# 0x02.net
KiCad netlist of a schematic drawn in EAGLE
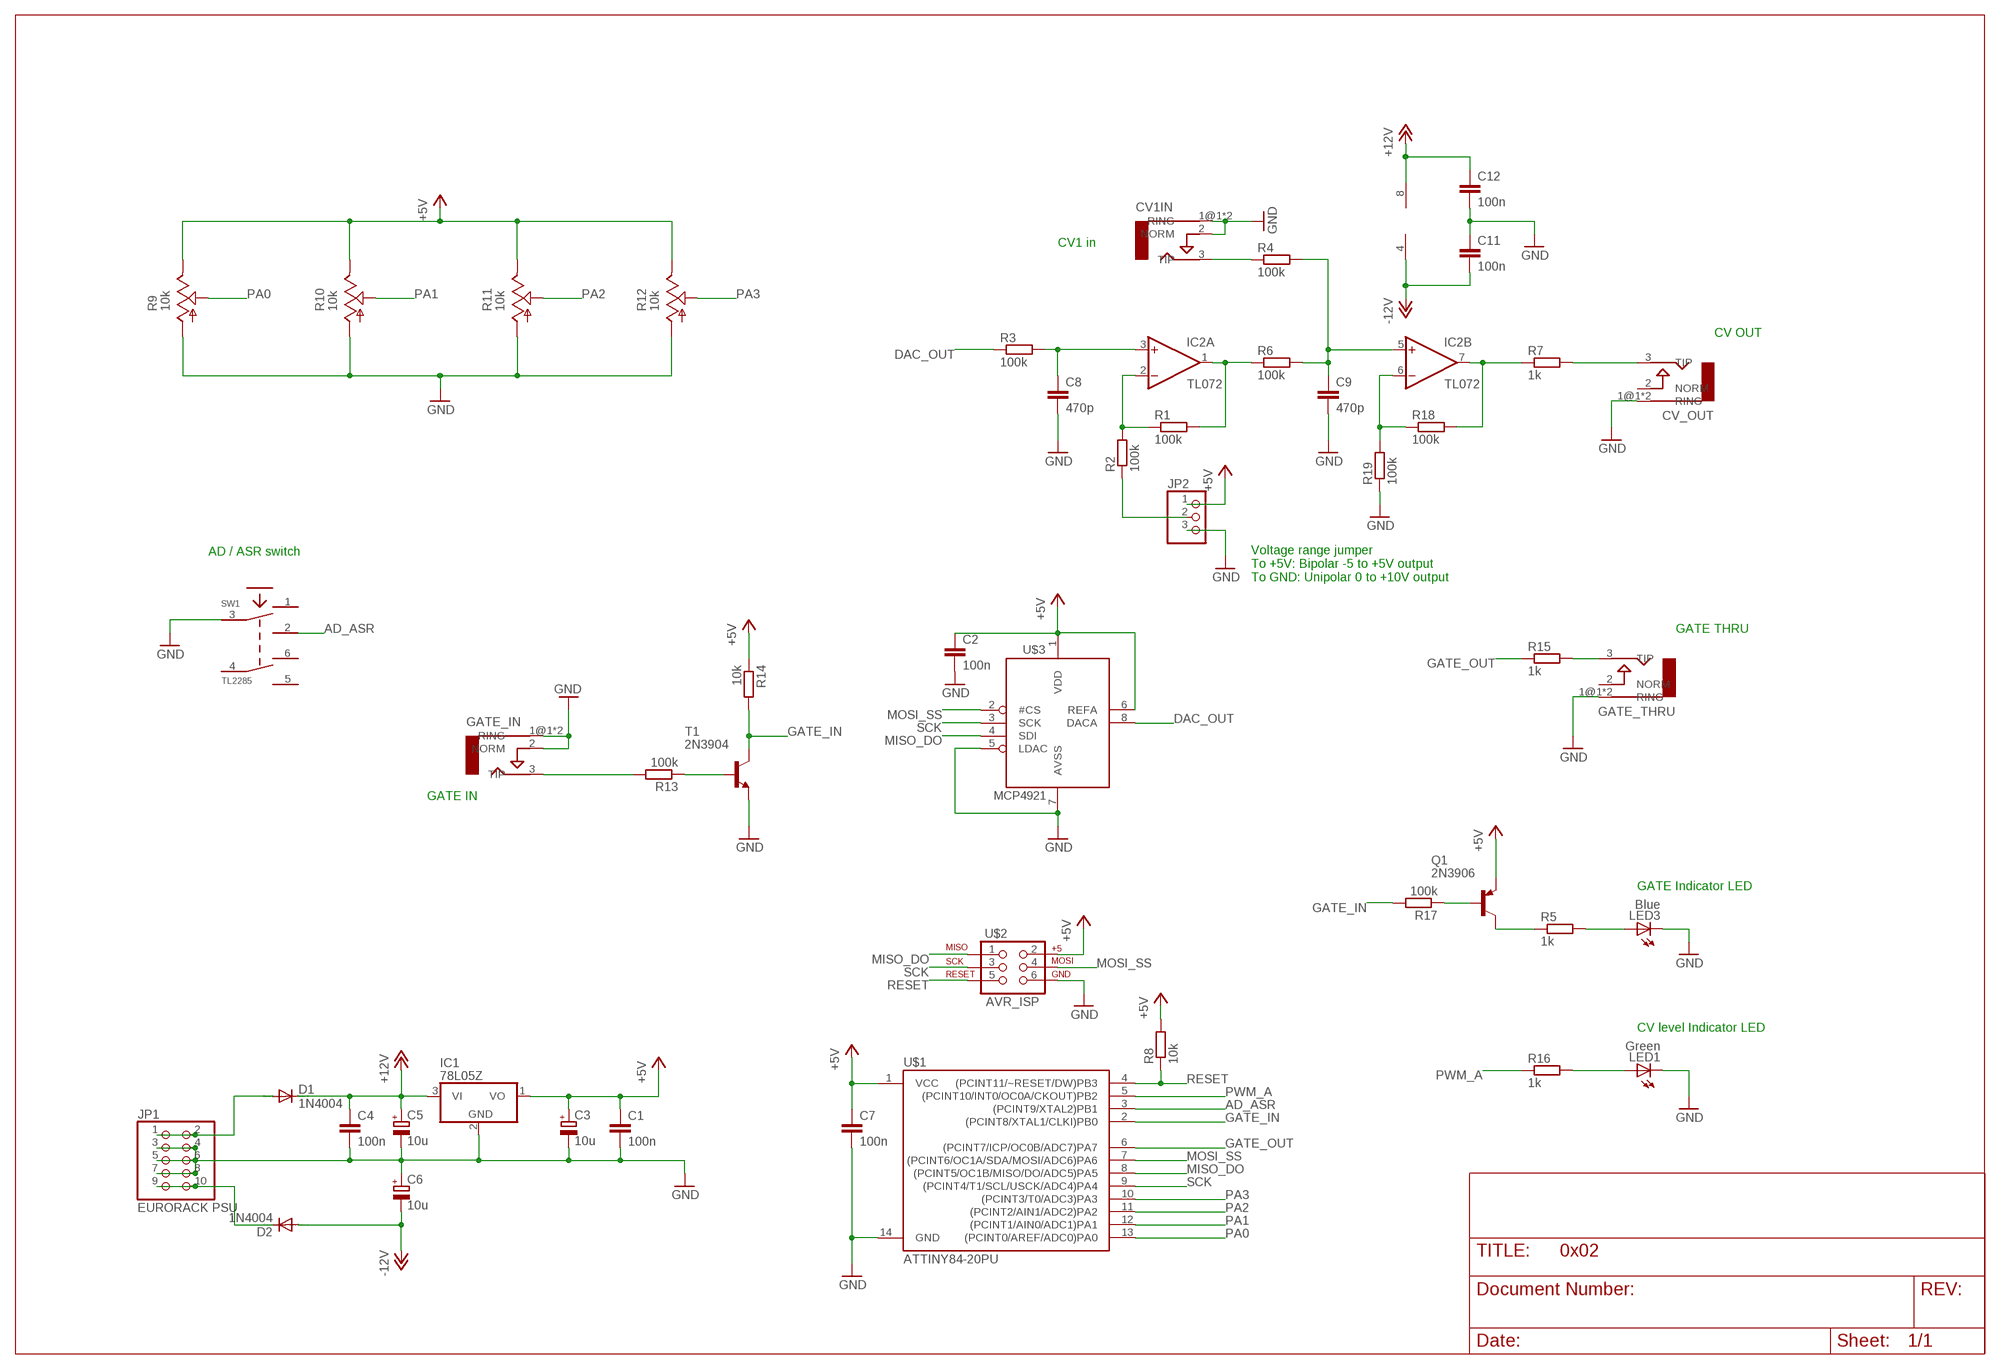
[diagram p0: schematic, sheet 1]

(export (version "E")
  (design (tool "Eeschema 10.0.6"))
  (components
    (comp (ref "C1")
      (value "100n")
      (footprint "eagle-import:C025-025X050")
      (libsource (lib "eagle-import") (part "C-EU025-025X050"))
    )
    (comp (ref "C2")
      (value "100n")
      (footprint "eagle-import:C025-025X050")
      (libsource (lib "eagle-import") (part "C-EU025-025X050"))
    )
    (comp (ref "C3")
      (value "10u")
      (footprint "eagle-import:E2,5-5")
      (libsource (lib "eagle-import") (part "CPOL-EUE2.5-5"))
    )
    (comp (ref "C4")
      (value "100n")
      (footprint "eagle-import:C025-025X050")
      (libsource (lib "eagle-import") (part "C-EU025-025X050"))
    )
    (comp (ref "C5")
      (value "10u")
      (footprint "eagle-import:E2,5-5")
      (libsource (lib "eagle-import") (part "CPOL-EUE2.5-5"))
    )
    (comp (ref "C6")
      (value "10u")
      (footprint "eagle-import:E2,5-5")
      (libsource (lib "eagle-import") (part "CPOL-EUE2.5-5"))
    )
    (comp (ref "C7")
      (value "100n")
      (footprint "eagle-import:C025-025X050")
      (libsource (lib "eagle-import") (part "C-EU025-025X050"))
    )
    (comp (ref "C8")
      (value "470p")
      (footprint "eagle-import:C025-025X050")
      (libsource (lib "eagle-import") (part "C-EU025-025X050"))
    )
    (comp (ref "C9")
      (value "470p")
      (footprint "eagle-import:C025-025X050")
      (libsource (lib "eagle-import") (part "C-EU025-025X050"))
    )
    (comp (ref "C11")
      (value "100n")
      (footprint "eagle-import:C025-025X050")
      (libsource (lib "eagle-import") (part "C-EU025-025X050"))
    )
    (comp (ref "C12")
      (value "100n")
      (footprint "eagle-import:C025-025X050")
      (libsource (lib "eagle-import") (part "C-EU025-025X050"))
    )
    (comp (ref "CV1IN")
      (value "AUDIO-JACKERTHENVAR")
      (footprint "eagle-import:ERTHENVAR-JACK")
      (libsource (lib "eagle-import") (part "AUDIO-JACKERTHENVAR"))
    )
    (comp (ref "CV_OUT")
      (value "CV_OUT")
      (footprint "eagle-import:ERTHENVAR-JACK")
      (libsource (lib "eagle-import") (part "AUDIO-JACKERTHENVAR"))
    )
    (comp (ref "D1")
      (value "1N4004")
      (footprint "eagle-import:DO41-10")
      (libsource (lib "eagle-import") (part "1N4004"))
    )
    (comp (ref "D2")
      (value "1N4004")
      (footprint "eagle-import:DO41-10")
      (libsource (lib "eagle-import") (part "1N4004"))
    )
    (comp (ref "GATE_IN")
      (value "AUDIO-JACKERTHENVAR")
      (footprint "eagle-import:ERTHENVAR-JACK")
      (libsource (lib "eagle-import") (part "AUDIO-JACKERTHENVAR"))
    )
    (comp (ref "GATE_THRU")
      (value "CV_OUT")
      (footprint "eagle-import:ERTHENVAR-JACK")
      (libsource (lib "eagle-import") (part "AUDIO-JACKERTHENVAR"))
    )
    (comp (ref "IC1")
      (value "78L05Z")
      (footprint "eagle-import:TO92")
      (libsource (lib "eagle-import") (part "78ZL05"))
    )
    (comp (ref "IC2")
      (value "TL072")
      (footprint "eagle-import:DIL08")
      (libsource (lib "eagle-import") (part "TL072P"))
    )
    (comp (ref "JP1")
      (value "EURORACK PSU")
      (footprint "eagle-import:2X05")
      (libsource (lib "eagle-import") (part "PINHD-2X5"))
    )
    (comp (ref "JP2")
      (value "PINHD-1X3")
      (footprint "eagle-import:1X03")
      (libsource (lib "eagle-import") (part "PINHD-1X3"))
    )
    (comp (ref "LED1")
      (value "Green")
      (footprint "eagle-import:LED5MM")
      (libsource (lib "eagle-import") (part "LED5MM"))
    )
    (comp (ref "LED3")
      (value "Blue")
      (footprint "eagle-import:LED5MM")
      (libsource (lib "eagle-import") (part "LED5MM"))
    )
    (comp (ref "Q1")
      (value "2N3906")
      (footprint "eagle-import:TO92")
      (libsource (lib "eagle-import") (part "2N3906"))
    )
    (comp (ref "R1")
      (value "100k")
      (footprint "eagle-import:0207_2V")
      (libsource (lib "eagle-import") (part "R-EU_0207/2V"))
    )
    (comp (ref "R2")
      (value "100k")
      (footprint "eagle-import:0207_2V")
      (libsource (lib "eagle-import") (part "R-EU_0207/2V"))
    )
    (comp (ref "R3")
      (value "100k")
      (footprint "eagle-import:0207_2V")
      (libsource (lib "eagle-import") (part "R-EU_0207/2V"))
    )
    (comp (ref "R4")
      (value "100k")
      (footprint "eagle-import:0207_2V")
      (libsource (lib "eagle-import") (part "R-EU_0207/2V"))
    )
    (comp (ref "R5")
      (value "1k")
      (footprint "eagle-import:0207_2V")
      (libsource (lib "eagle-import") (part "R-EU_0207/2V"))
    )
    (comp (ref "R6")
      (value "100k")
      (footprint "eagle-import:0207_2V")
      (libsource (lib "eagle-import") (part "R-EU_0207/2V"))
    )
    (comp (ref "R7")
      (value "1k")
      (footprint "eagle-import:0207_2V")
      (libsource (lib "eagle-import") (part "R-EU_0207/2V"))
    )
    (comp (ref "R8")
      (value "10k")
      (footprint "eagle-import:0207_2V")
      (libsource (lib "eagle-import") (part "R-EU_0207/2V"))
    )
    (comp (ref "R9")
      (value "10k")
      (footprint "eagle-import:ALPS_POT_VERTICAL")
      (libsource (lib "eagle-import") (part "POT_USVERTICAL"))
    )
    (comp (ref "R10")
      (value "10k")
      (footprint "eagle-import:ALPS_POT_VERTICAL")
      (libsource (lib "eagle-import") (part "POT_USVERTICAL"))
    )
    (comp (ref "R11")
      (value "10k")
      (footprint "eagle-import:ALPS_POT_VERTICAL")
      (libsource (lib "eagle-import") (part "POT_USVERTICAL"))
    )
    (comp (ref "R12")
      (value "10k")
      (footprint "eagle-import:ALPS_POT_VERTICAL")
      (libsource (lib "eagle-import") (part "POT_USVERTICAL"))
    )
    (comp (ref "R13")
      (value "100k")
      (footprint "eagle-import:0207_2V")
      (libsource (lib "eagle-import") (part "R-EU_0207/2V"))
    )
    (comp (ref "R14")
      (value "10k")
      (footprint "eagle-import:0207_2V")
      (libsource (lib "eagle-import") (part "R-EU_0207/2V"))
    )
    (comp (ref "R15")
      (value "1k")
      (footprint "eagle-import:0207_2V")
      (libsource (lib "eagle-import") (part "R-EU_0207/2V"))
    )
    (comp (ref "R16")
      (value "1k")
      (footprint "eagle-import:0207_2V")
      (libsource (lib "eagle-import") (part "R-EU_0207/2V"))
    )
    (comp (ref "R17")
      (value "100k")
      (footprint "eagle-import:0207_2V")
      (libsource (lib "eagle-import") (part "R-EU_0207/2V"))
    )
    (comp (ref "R18")
      (value "100k")
      (footprint "eagle-import:0207_2V")
      (libsource (lib "eagle-import") (part "R-EU_0207/2V"))
    )
    (comp (ref "R19")
      (value "100k")
      (footprint "eagle-import:0207_2V")
      (libsource (lib "eagle-import") (part "R-EU_0207/2V"))
    )
    (comp (ref "SW1")
      (value "TL2285")
      (footprint "eagle-import:TL2285_PCB")
      (libsource (lib "eagle-import") (part "TL2285"))
    )
    (comp (ref "T1")
      (value "2N3904")
      (footprint "eagle-import:TO92")
      (libsource (lib "eagle-import") (part "2N3904"))
    )
    (comp (ref "U$1")
      (value "ATTINY84-20PU")
      (footprint "eagle-import:DIL14")
      (libsource (lib "eagle-import") (part "ATTINY84ATTINY84-20PU"))
    )
    (comp (ref "U$2")
      (value "AVR_ISP")
      (footprint "eagle-import:2X3")
      (libsource (lib "eagle-import") (part "AVR_SPI_PRG_6PTH"))
    )
    (comp (ref "U$3")
      (value "MCP4921")
      (footprint "eagle-import:DIL08")
      (libsource (lib "eagle-import") (part "MCP4921"))
    )
  )
  (nets
    (net (code "1") (name "+5V") (class "Default")
      (node (ref "C1") (pin "1") (pinfunction "1_1") (pintype "passive"))
      (node (ref "C2") (pin "1") (pinfunction "1_1") (pintype "passive"))
      (node (ref "C3") (pin "+") (pinfunction "+_+") (pintype "passive"))
      (node (ref "C7") (pin "1") (pinfunction "1_1") (pintype "passive"))
      (node (ref "IC1") (pin "1") (pinfunction "VO_1") (pintype "passive"))
      (node (ref "JP2") (pin "1") (pinfunction "1_1") (pintype "passive"))
      (node (ref "Q1") (pin "3") (pinfunction "E_3") (pintype "passive"))
      (node (ref "R10") (pin "P$1") (pinfunction "E_P$1") (pintype "passive"))
      (node (ref "R11") (pin "P$1") (pinfunction "E_P$1") (pintype "passive"))
      (node (ref "R12") (pin "P$1") (pinfunction "E_P$1") (pintype "passive"))
      (node (ref "R14") (pin "1") (pinfunction "1_1") (pintype "passive"))
      (node (ref "R8") (pin "2") (pinfunction "2_2") (pintype "passive"))
      (node (ref "R9") (pin "P$1") (pinfunction "E_P$1") (pintype "passive"))
      (node (ref "U$1") (pin "1") (pinfunction "VCC_1") (pintype "bidirectional"))
      (node (ref "U$2") (pin "2") (pinfunction "2_2") (pintype "passive"))
      (node (ref "U$3") (pin "1") (pinfunction "VDD_1") (pintype "power_in"))
      (node (ref "U$3") (pin "6") (pinfunction "REFA_6") (pintype "input"))
    )
    (net (code "2") (name "+12V") (class "Default")
      (node (ref "C12") (pin "1") (pinfunction "1_1") (pintype "passive"))
      (node (ref "C4") (pin "1") (pinfunction "1_1") (pintype "passive"))
      (node (ref "C5") (pin "+") (pinfunction "+_+") (pintype "passive"))
      (node (ref "D1") (pin "C") (pinfunction "C_C") (pintype "passive"))
      (node (ref "IC1") (pin "3") (pinfunction "VI_3") (pintype "input"))
      (node (ref "IC2") (pin "8") (pinfunction "V+_8") (pintype "power_in"))
    )
    (net (code "3") (name "-12V") (class "Default")
      (node (ref "C11") (pin "2") (pinfunction "2_2") (pintype "passive"))
      (node (ref "C6") (pin "-") (pinfunction "-_-") (pintype "passive"))
      (node (ref "D2") (pin "A") (pinfunction "A_A") (pintype "passive"))
      (node (ref "IC2") (pin "4") (pinfunction "V-_4") (pintype "power_in"))
    )
    (net (code "4") (name "/AD_ASR") (class "Default")
      (node (ref "SW1") (pin "2") (pinfunction "P2_2") (pintype "bidirectional"))
      (node (ref "U$1") (pin "3") (pinfunction "(PCINT9/XTAL2)PB1_3") (pintype "bidirectional"))
    )
    (net (code "5") (name "/DAC_OUT") (class "Default")
      (node (ref "R3") (pin "1") (pinfunction "1_1") (pintype "passive"))
      (node (ref "U$3") (pin "8") (pinfunction "DACA_8") (pintype "output"))
    )
    (net (code "6") (name "/GATE_IN") (class "Default")
      (node (ref "R14") (pin "2") (pinfunction "2_2") (pintype "passive"))
      (node (ref "R17") (pin "2") (pinfunction "2_2") (pintype "passive"))
      (node (ref "T1") (pin "1") (pinfunction "C_1") (pintype "passive"))
      (node (ref "U$1") (pin "2") (pinfunction "(PCINT8/XTAL1/CLKI)PB0_2") (pintype "bidirectional"))
    )
    (net (code "7") (name "/GATE_OUT") (class "Default")
      (node (ref "R15") (pin "1") (pinfunction "1_1") (pintype "passive"))
      (node (ref "U$1") (pin "6") (pinfunction "(PCINT7/ICP/OC0B/ADC7)PA7_6") (pintype "bidirectional"))
    )
    (net (code "8") (name "/MISO_DO") (class "Default")
      (node (ref "U$1") (pin "8") (pinfunction "(PCINT5/OC1B/MISO/DO/ADC5)PA5_8") (pintype "bidirectional"))
      (node (ref "U$2") (pin "1") (pinfunction "1_1") (pintype "passive"))
      (node (ref "U$3") (pin "4") (pinfunction "SDI_4") (pintype "input"))
    )
    (net (code "9") (name "/MOSI_SS") (class "Default")
      (node (ref "U$1") (pin "7") (pinfunction "(PCINT6/OC1A/SDA/MOSI/ADC6)PA6_7") (pintype "bidirectional"))
      (node (ref "U$2") (pin "4") (pinfunction "4_4") (pintype "passive"))
      (node (ref "U$3") (pin "2") (pinfunction "#CS_2") (pintype "input"))
    )
    (net (code "10") (name "/PA0") (class "Default")
      (node (ref "R9") (pin "P$2") (pinfunction "S_P$2") (pintype "passive"))
      (node (ref "U$1") (pin "13") (pinfunction "(PCINT0/AREF/ADC0)PA0_13") (pintype "bidirectional"))
    )
    (net (code "11") (name "/PA1") (class "Default")
      (node (ref "R10") (pin "P$2") (pinfunction "S_P$2") (pintype "passive"))
      (node (ref "U$1") (pin "12") (pinfunction "(PCINT1/AIN0/ADC1)PA1_12") (pintype "bidirectional"))
    )
    (net (code "12") (name "/PA2") (class "Default")
      (node (ref "R11") (pin "P$2") (pinfunction "S_P$2") (pintype "passive"))
      (node (ref "U$1") (pin "11") (pinfunction "(PCINT2/AIN1/ADC2)PA2_11") (pintype "bidirectional"))
    )
    (net (code "13") (name "/PA3") (class "Default")
      (node (ref "R12") (pin "P$2") (pinfunction "S_P$2") (pintype "passive"))
      (node (ref "U$1") (pin "10") (pinfunction "(PCINT3/T0/ADC3)PA3_10") (pintype "bidirectional"))
    )
    (net (code "14") (name "/PWM_A") (class "Default")
      (node (ref "R16") (pin "1") (pinfunction "1_1") (pintype "passive"))
      (node (ref "U$1") (pin "5") (pinfunction "(PCINT10/INT0/OC0A/CKOUT)PB2_5") (pintype "bidirectional"))
    )
    (net (code "15") (name "/RESET") (class "Default")
      (node (ref "R8") (pin "1") (pinfunction "1_1") (pintype "passive"))
      (node (ref "U$1") (pin "4") (pinfunction "(PCINT11/~{RESET/DW})PB3_4") (pintype "bidirectional"))
      (node (ref "U$2") (pin "5") (pinfunction "5_5") (pintype "passive"))
    )
    (net (code "16") (name "/SCK") (class "Default")
      (node (ref "U$1") (pin "9") (pinfunction "(PCINT4/T1/SCL/USCK/ADC4)PA4_9") (pintype "bidirectional"))
      (node (ref "U$2") (pin "3") (pinfunction "3_3") (pintype "passive"))
      (node (ref "U$3") (pin "3") (pinfunction "SCK_3") (pintype "input"))
    )
    (net (code "17") (name "GND") (class "Default")
      (node (ref "C1") (pin "2") (pinfunction "2_2") (pintype "passive"))
      (node (ref "C11") (pin "1") (pinfunction "1_1") (pintype "passive"))
      (node (ref "C12") (pin "2") (pinfunction "2_2") (pintype "passive"))
      (node (ref "C2") (pin "2") (pinfunction "2_2") (pintype "passive"))
      (node (ref "C3") (pin "-") (pinfunction "-_-") (pintype "passive"))
      (node (ref "C4") (pin "2") (pinfunction "2_2") (pintype "passive"))
      (node (ref "C5") (pin "-") (pinfunction "-_-") (pintype "passive"))
      (node (ref "C6") (pin "+") (pinfunction "+_+") (pintype "passive"))
      (node (ref "C7") (pin "2") (pinfunction "2_2") (pintype "passive"))
      (node (ref "C8") (pin "2") (pinfunction "2_2") (pintype "passive"))
      (node (ref "C9") (pin "2") (pinfunction "2_2") (pintype "passive"))
      (node (ref "CV1IN") (pin "1@1") (pinfunction "RING_1@1") (pintype "bidirectional"))
      (node (ref "CV1IN") (pin "1@2") (pinfunction "RING_1@2") (pintype "bidirectional"))
      (node (ref "CV1IN") (pin "2") (pinfunction "NORM_2") (pintype "bidirectional"))
      (node (ref "CV_OUT") (pin "1@1") (pinfunction "RING_1@1") (pintype "bidirectional"))
      (node (ref "CV_OUT") (pin "1@2") (pinfunction "RING_1@2") (pintype "bidirectional"))
      (node (ref "GATE_IN") (pin "1@1") (pinfunction "RING_1@1") (pintype "bidirectional"))
      (node (ref "GATE_IN") (pin "1@2") (pinfunction "RING_1@2") (pintype "bidirectional"))
      (node (ref "GATE_IN") (pin "2") (pinfunction "NORM_2") (pintype "bidirectional"))
      (node (ref "GATE_THRU") (pin "1@1") (pinfunction "RING_1@1") (pintype "bidirectional"))
      (node (ref "GATE_THRU") (pin "1@2") (pinfunction "RING_1@2") (pintype "bidirectional"))
      (node (ref "IC1") (pin "2") (pinfunction "GND_2") (pintype "passive"))
      (node (ref "JP1") (pin "3") (pinfunction "3_3") (pintype "passive"))
      (node (ref "JP1") (pin "4") (pinfunction "4_4") (pintype "passive"))
      (node (ref "JP1") (pin "5") (pinfunction "5_5") (pintype "passive"))
      (node (ref "JP1") (pin "6") (pinfunction "6_6") (pintype "passive"))
      (node (ref "JP1") (pin "7") (pinfunction "7_7") (pintype "passive"))
      (node (ref "JP1") (pin "8") (pinfunction "8_8") (pintype "passive"))
      (node (ref "JP2") (pin "3") (pinfunction "3_3") (pintype "passive"))
      (node (ref "LED1") (pin "K") (pinfunction "C_K") (pintype "passive"))
      (node (ref "LED3") (pin "K") (pinfunction "C_K") (pintype "passive"))
      (node (ref "R10") (pin "P$3") (pinfunction "A_P$3") (pintype "passive"))
      (node (ref "R11") (pin "P$3") (pinfunction "A_P$3") (pintype "passive"))
      (node (ref "R12") (pin "P$3") (pinfunction "A_P$3") (pintype "passive"))
      (node (ref "R19") (pin "1") (pinfunction "1_1") (pintype "passive"))
      (node (ref "R9") (pin "P$3") (pinfunction "A_P$3") (pintype "passive"))
      (node (ref "SW1") (pin "3") (pinfunction "P3_3") (pintype "bidirectional"))
      (node (ref "T1") (pin "3") (pinfunction "E_3") (pintype "passive"))
      (node (ref "U$1") (pin "14") (pinfunction "GND_14") (pintype "bidirectional"))
      (node (ref "U$2") (pin "6") (pinfunction "6_6") (pintype "passive"))
      (node (ref "U$3") (pin "5") (pinfunction "LDAC_5") (pintype "input"))
      (node (ref "U$3") (pin "7") (pinfunction "AVSS_7") (pintype "power_in"))
    )
    (net (code "18") (name "Net-(CV1IN-TIP)") (class "Default")
      (node (ref "CV1IN") (pin "3") (pinfunction "TIP_3") (pintype "bidirectional"))
      (node (ref "R4") (pin "1") (pinfunction "1_1") (pintype "passive"))
    )
    (net (code "19") (name "Net-(CV_OUT-TIP)") (class "Default")
      (node (ref "CV_OUT") (pin "3") (pinfunction "TIP_3") (pintype "bidirectional"))
      (node (ref "R7") (pin "2") (pinfunction "2_2") (pintype "passive"))
    )
    (net (code "20") (name "Net-(D1-PadA)") (class "Default")
      (node (ref "D1") (pin "A") (pinfunction "A_A") (pintype "passive"))
      (node (ref "JP1") (pin "1") (pinfunction "1_1") (pintype "passive"))
      (node (ref "JP1") (pin "2") (pinfunction "2_2") (pintype "passive"))
    )
    (net (code "21") (name "Net-(D2-PadC)") (class "Default")
      (node (ref "D2") (pin "C") (pinfunction "C_C") (pintype "passive"))
      (node (ref "JP1") (pin "10") (pinfunction "10_10") (pintype "passive"))
      (node (ref "JP1") (pin "9") (pinfunction "9_9") (pintype "passive"))
    )
    (net (code "22") (name "Net-(GATE_IN-TIP)") (class "Default")
      (node (ref "GATE_IN") (pin "3") (pinfunction "TIP_3") (pintype "bidirectional"))
      (node (ref "R13") (pin "2") (pinfunction "2_2") (pintype "passive"))
    )
    (net (code "23") (name "Net-(GATE_THRU-TIP)") (class "Default")
      (node (ref "GATE_THRU") (pin "3") (pinfunction "TIP_3") (pintype "bidirectional"))
      (node (ref "R15") (pin "2") (pinfunction "2_2") (pintype "passive"))
    )
    (net (code "24") (name "Net-(IC2A-+IN)") (class "Default")
      (node (ref "C8") (pin "1") (pinfunction "1_1") (pintype "passive"))
      (node (ref "IC2") (pin "3") (pinfunction "+IN_3") (pintype "input"))
      (node (ref "R3") (pin "2") (pinfunction "2_2") (pintype "passive"))
    )
    (net (code "25") (name "Net-(IC2A--IN)") (class "Default")
      (node (ref "IC2") (pin "2") (pinfunction "-IN_2") (pintype "input"))
      (node (ref "R1") (pin "1") (pinfunction "1_1") (pintype "passive"))
      (node (ref "R2") (pin "2") (pinfunction "2_2") (pintype "passive"))
    )
    (net (code "26") (name "Net-(IC2A-OUT)") (class "Default")
      (node (ref "IC2") (pin "1") (pinfunction "OUT_1") (pintype "output"))
      (node (ref "R1") (pin "2") (pinfunction "2_2") (pintype "passive"))
      (node (ref "R6") (pin "1") (pinfunction "1_1") (pintype "passive"))
    )
    (net (code "27") (name "Net-(IC2B-+IN)") (class "Default")
      (node (ref "C9") (pin "1") (pinfunction "1_1") (pintype "passive"))
      (node (ref "IC2") (pin "5") (pinfunction "+IN_5") (pintype "input"))
      (node (ref "R4") (pin "2") (pinfunction "2_2") (pintype "passive"))
      (node (ref "R6") (pin "2") (pinfunction "2_2") (pintype "passive"))
    )
    (net (code "28") (name "Net-(IC2B--IN)") (class "Default")
      (node (ref "IC2") (pin "6") (pinfunction "-IN_6") (pintype "input"))
      (node (ref "R18") (pin "1") (pinfunction "1_1") (pintype "passive"))
      (node (ref "R19") (pin "2") (pinfunction "2_2") (pintype "passive"))
    )
    (net (code "29") (name "Net-(IC2B-OUT)") (class "Default")
      (node (ref "IC2") (pin "7") (pinfunction "OUT_7") (pintype "output"))
      (node (ref "R18") (pin "2") (pinfunction "2_2") (pintype "passive"))
      (node (ref "R7") (pin "1") (pinfunction "1_1") (pintype "passive"))
    )
    (net (code "30") (name "Net-(JP2-Pad2)") (class "Default")
      (node (ref "JP2") (pin "2") (pinfunction "2_2") (pintype "passive"))
      (node (ref "R2") (pin "1") (pinfunction "1_1") (pintype "passive"))
    )
    (net (code "31") (name "Net-(LED1-PadA)") (class "Default")
      (node (ref "LED1") (pin "A") (pinfunction "A_A") (pintype "passive"))
      (node (ref "R16") (pin "2") (pinfunction "2_2") (pintype "passive"))
    )
    (net (code "32") (name "Net-(LED3-PadA)") (class "Default")
      (node (ref "LED3") (pin "A") (pinfunction "A_A") (pintype "passive"))
      (node (ref "R5") (pin "2") (pinfunction "2_2") (pintype "passive"))
    )
    (net (code "33") (name "Net-(Q1-B)") (class "Default")
      (node (ref "Q1") (pin "2") (pinfunction "B_2") (pintype "passive"))
      (node (ref "R17") (pin "1") (pinfunction "1_1") (pintype "passive"))
    )
    (net (code "34") (name "Net-(Q1-C)") (class "Default")
      (node (ref "Q1") (pin "1") (pinfunction "C_1") (pintype "passive"))
      (node (ref "R5") (pin "1") (pinfunction "1_1") (pintype "passive"))
    )
    (net (code "35") (name "Net-(T1-B)") (class "Default")
      (node (ref "R13") (pin "1") (pinfunction "1_1") (pintype "passive"))
      (node (ref "T1") (pin "2") (pinfunction "B_2") (pintype "passive"))
    )
    (net (code "36") (name "unconnected-(CV_OUT-NORM-Pad2)") (class "Default")
      (node (ref "CV_OUT") (pin "2") (pinfunction "NORM_2") (pintype "bidirectional"))
    )
    (net (code "37") (name "unconnected-(GATE_THRU-NORM-Pad2)") (class "Default")
      (node (ref "GATE_THRU") (pin "2") (pinfunction "NORM_2") (pintype "bidirectional"))
    )
    (net (code "38") (name "unconnected-(SW1-P1-Pad1)") (class "Default")
      (node (ref "SW1") (pin "1") (pinfunction "P1_1") (pintype "bidirectional"))
    )
    (net (code "39") (name "unconnected-(SW1-P4-Pad4)") (class "Default")
      (node (ref "SW1") (pin "4") (pinfunction "P4_4") (pintype "bidirectional"))
    )
    (net (code "40") (name "unconnected-(SW1-P5-Pad5)") (class "Default")
      (node (ref "SW1") (pin "5") (pinfunction "P5_5") (pintype "bidirectional"))
    )
    (net (code "41") (name "unconnected-(SW1-P6-Pad6)") (class "Default")
      (node (ref "SW1") (pin "6") (pinfunction "P6_6") (pintype "bidirectional"))
    )
  )
)
